# ServoExpanderPCB.net
KiCad netlist of a schematic drawn in Altium Designer
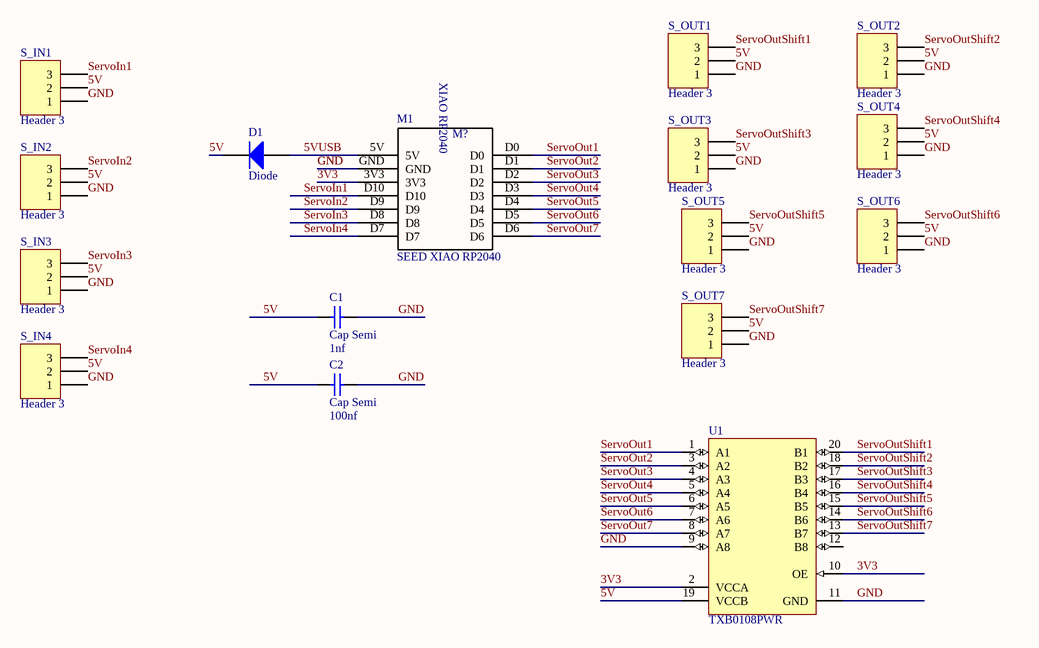
[diagram p0: ServoExpanderPCB.SchDoc]

(export (version "E")
  (design (tool "Eeschema 10.0.6"))
  (components
    (comp (ref "C1")
      (value "Cap Semi")
      (footprint "6-0805_M")
      (description "Capacitor (Semiconductor SIM Model)")
      (fields (field (name "ALTIUM_VALUE") "1nf") (field (name "PUBLISHER") "Altium Limited"))
      (libsource (lib "Miscellaneous Devices") (part "Cap Semi"))
    )
    (comp (ref "C2")
      (value "Cap Semi")
      (footprint "6-0805_M")
      (description "Capacitor (Semiconductor SIM Model)")
      (fields (field (name "ALTIUM_VALUE") "100nf") (field (name "PUBLISHER") "Altium Limited"))
      (libsource (lib "Miscellaneous Devices") (part "Cap Semi"))
    )
    (comp (ref "D1")
      (value "Diode")
      (footprint "6-0805_M")
      (description "Default Diode")
      (fields (field (name "PUBLISHER") "Altium Limited"))
      (libsource (lib "Miscellaneous Devices") (part "Diode"))
    )
    (comp (ref "M1")
      (value "SEED XIAO RP2040")
      (footprint "XIAO RP2040")
      (libsource (lib "RP2040Library") (part "SEED XIAO RP2040"))
    )
    (comp (ref "S_IN1")
      (value "Header 3")
      (footprint "HDR1X3")
      (description "Header, 3-Pin")
      (fields (field (name "PUBLISHER") "Altium Limited"))
      (libsource (lib "Miscellaneous Connectors") (part "Header 3"))
    )
    (comp (ref "S_IN2")
      (value "Header 3")
      (footprint "HDR1X3")
      (description "Header, 3-Pin")
      (fields (field (name "PUBLISHER") "Altium Limited"))
      (libsource (lib "Miscellaneous Connectors") (part "Header 3"))
    )
    (comp (ref "S_IN3")
      (value "Header 3")
      (footprint "HDR1X3")
      (description "Header, 3-Pin")
      (fields (field (name "PUBLISHER") "Altium Limited"))
      (libsource (lib "Miscellaneous Connectors") (part "Header 3"))
    )
    (comp (ref "S_IN4")
      (value "Header 3")
      (footprint "HDR1X3")
      (description "Header, 3-Pin")
      (fields (field (name "PUBLISHER") "Altium Limited"))
      (libsource (lib "Miscellaneous Connectors") (part "Header 3"))
    )
    (comp (ref "S_OUT1")
      (value "Header 3")
      (footprint "HDR1X3")
      (description "Header, 3-Pin")
      (fields (field (name "PUBLISHER") "Altium Limited"))
      (libsource (lib "Miscellaneous Connectors") (part "Header 3"))
    )
    (comp (ref "S_OUT2")
      (value "Header 3")
      (footprint "HDR1X3")
      (description "Header, 3-Pin")
      (fields (field (name "PUBLISHER") "Altium Limited"))
      (libsource (lib "Miscellaneous Connectors") (part "Header 3"))
    )
    (comp (ref "S_OUT3")
      (value "Header 3")
      (footprint "HDR1X3")
      (description "Header, 3-Pin")
      (fields (field (name "PUBLISHER") "Altium Limited"))
      (libsource (lib "Miscellaneous Connectors") (part "Header 3"))
    )
    (comp (ref "S_OUT4")
      (value "Header 3")
      (footprint "HDR1X3")
      (description "Header, 3-Pin")
      (fields (field (name "PUBLISHER") "Altium Limited"))
      (libsource (lib "Miscellaneous Connectors") (part "Header 3"))
    )
    (comp (ref "S_OUT5")
      (value "Header 3")
      (footprint "HDR1X3")
      (description "Header, 3-Pin")
      (fields (field (name "PUBLISHER") "Altium Limited"))
      (libsource (lib "Miscellaneous Connectors") (part "Header 3"))
    )
    (comp (ref "S_OUT6")
      (value "Header 3")
      (footprint "HDR1X3")
      (description "Header, 3-Pin")
      (fields (field (name "PUBLISHER") "Altium Limited"))
      (libsource (lib "Miscellaneous Connectors") (part "Header 3"))
    )
    (comp (ref "S_OUT7")
      (value "Header 3")
      (footprint "HDR1X3")
      (description "Header, 3-Pin")
      (fields (field (name "PUBLISHER") "Altium Limited"))
      (libsource (lib "Miscellaneous Connectors") (part "Header 3"))
    )
    (comp (ref "U1")
      (value "TXB0108PWR")
      (footprint "PW0020A_L")
      (fields (field (name "MANUFACTURER") "Texas Instruments"))
      (libsource (lib "Altium Content Vault") (part "TI-TXB0108-PW-20"))
    )
  )
  (nets
    (net (code "1") (name "/3V3") (class "Default")
      (node (ref "M1") (pin "3V3") (pinfunction "3V3_3V3") (pintype "passive"))
      (node (ref "U1") (pin "10") (pinfunction "OE_10") (pintype "input"))
      (node (ref "U1") (pin "2") (pinfunction "VCCA_2") (pintype "power_in"))
    )
    (net (code "2") (name "/5V") (class "Default")
      (node (ref "C1") (pin "1") (pinfunction "1_1") (pintype "passive"))
      (node (ref "C2") (pin "1") (pinfunction "1_1") (pintype "passive"))
      (node (ref "D1") (pin "2") (pinfunction "K_2") (pintype "passive"))
      (node (ref "S_IN1") (pin "2") (pinfunction "2_2") (pintype "passive"))
      (node (ref "S_IN2") (pin "2") (pinfunction "2_2") (pintype "passive"))
      (node (ref "S_IN3") (pin "2") (pinfunction "2_2") (pintype "passive"))
      (node (ref "S_IN4") (pin "2") (pinfunction "2_2") (pintype "passive"))
      (node (ref "S_OUT1") (pin "2") (pinfunction "2_2") (pintype "passive"))
      (node (ref "S_OUT2") (pin "2") (pinfunction "2_2") (pintype "passive"))
      (node (ref "S_OUT3") (pin "2") (pinfunction "2_2") (pintype "passive"))
      (node (ref "S_OUT4") (pin "2") (pinfunction "2_2") (pintype "passive"))
      (node (ref "S_OUT5") (pin "2") (pinfunction "2_2") (pintype "passive"))
      (node (ref "S_OUT6") (pin "2") (pinfunction "2_2") (pintype "passive"))
      (node (ref "S_OUT7") (pin "2") (pinfunction "2_2") (pintype "passive"))
      (node (ref "U1") (pin "19") (pinfunction "VCCB_19") (pintype "power_in"))
    )
    (net (code "3") (name "/5VUSB") (class "Default")
      (node (ref "D1") (pin "1") (pinfunction "A_1") (pintype "passive"))
      (node (ref "M1") (pin "5V") (pinfunction "5V_5V") (pintype "passive"))
    )
    (net (code "4") (name "/GND") (class "Default")
      (node (ref "C1") (pin "2") (pinfunction "2_2") (pintype "passive"))
      (node (ref "C2") (pin "2") (pinfunction "2_2") (pintype "passive"))
      (node (ref "M1") (pin "GND") (pinfunction "GND_GND") (pintype "passive"))
      (node (ref "S_IN1") (pin "1") (pinfunction "1_1") (pintype "passive"))
      (node (ref "S_IN2") (pin "1") (pinfunction "1_1") (pintype "passive"))
      (node (ref "S_IN3") (pin "1") (pinfunction "1_1") (pintype "passive"))
      (node (ref "S_IN4") (pin "1") (pinfunction "1_1") (pintype "passive"))
      (node (ref "S_OUT1") (pin "1") (pinfunction "1_1") (pintype "passive"))
      (node (ref "S_OUT2") (pin "1") (pinfunction "1_1") (pintype "passive"))
      (node (ref "S_OUT3") (pin "1") (pinfunction "1_1") (pintype "passive"))
      (node (ref "S_OUT4") (pin "1") (pinfunction "1_1") (pintype "passive"))
      (node (ref "S_OUT5") (pin "1") (pinfunction "1_1") (pintype "passive"))
      (node (ref "S_OUT6") (pin "1") (pinfunction "1_1") (pintype "passive"))
      (node (ref "S_OUT7") (pin "1") (pinfunction "1_1") (pintype "passive"))
      (node (ref "U1") (pin "11") (pinfunction "GND_11") (pintype "power_in"))
      (node (ref "U1") (pin "9") (pinfunction "A8_9") (pintype "bidirectional"))
    )
    (net (code "5") (name "/ServoIn1") (class "Default")
      (node (ref "M1") (pin "D10") (pinfunction "D10_D10") (pintype "passive"))
      (node (ref "S_IN1") (pin "3") (pinfunction "3_3") (pintype "passive"))
    )
    (net (code "6") (name "/ServoIn2") (class "Default")
      (node (ref "M1") (pin "D9") (pinfunction "D9_D9") (pintype "passive"))
      (node (ref "S_IN2") (pin "3") (pinfunction "3_3") (pintype "passive"))
    )
    (net (code "7") (name "/ServoIn3") (class "Default")
      (node (ref "M1") (pin "D8") (pinfunction "D8_D8") (pintype "passive"))
      (node (ref "S_IN3") (pin "3") (pinfunction "3_3") (pintype "passive"))
    )
    (net (code "8") (name "/ServoIn4") (class "Default")
      (node (ref "M1") (pin "D7") (pinfunction "D7_D7") (pintype "passive"))
      (node (ref "S_IN4") (pin "3") (pinfunction "3_3") (pintype "passive"))
    )
    (net (code "9") (name "/ServoOut1") (class "Default")
      (node (ref "M1") (pin "D0") (pinfunction "D0_D0") (pintype "passive"))
      (node (ref "U1") (pin "1") (pinfunction "A1_1") (pintype "bidirectional"))
    )
    (net (code "10") (name "/ServoOut2") (class "Default")
      (node (ref "M1") (pin "D1") (pinfunction "D1_D1") (pintype "passive"))
      (node (ref "U1") (pin "3") (pinfunction "A2_3") (pintype "bidirectional"))
    )
    (net (code "11") (name "/ServoOut3") (class "Default")
      (node (ref "M1") (pin "D2") (pinfunction "D2_D2") (pintype "passive"))
      (node (ref "U1") (pin "4") (pinfunction "A3_4") (pintype "bidirectional"))
    )
    (net (code "12") (name "/ServoOut4") (class "Default")
      (node (ref "M1") (pin "D3") (pinfunction "D3_D3") (pintype "passive"))
      (node (ref "U1") (pin "5") (pinfunction "A4_5") (pintype "bidirectional"))
    )
    (net (code "13") (name "/ServoOut5") (class "Default")
      (node (ref "M1") (pin "D4") (pinfunction "D4_D4") (pintype "passive"))
      (node (ref "U1") (pin "6") (pinfunction "A5_6") (pintype "bidirectional"))
    )
    (net (code "14") (name "/ServoOut6") (class "Default")
      (node (ref "M1") (pin "D5") (pinfunction "D5_D5") (pintype "passive"))
      (node (ref "U1") (pin "7") (pinfunction "A6_7") (pintype "bidirectional"))
    )
    (net (code "15") (name "/ServoOut7") (class "Default")
      (node (ref "M1") (pin "D6") (pinfunction "D6_D6") (pintype "passive"))
      (node (ref "U1") (pin "8") (pinfunction "A7_8") (pintype "bidirectional"))
    )
    (net (code "16") (name "/ServoOutShift1") (class "Default")
      (node (ref "S_OUT1") (pin "3") (pinfunction "3_3") (pintype "passive"))
      (node (ref "U1") (pin "20") (pinfunction "B1_20") (pintype "bidirectional"))
    )
    (net (code "17") (name "/ServoOutShift2") (class "Default")
      (node (ref "S_OUT2") (pin "3") (pinfunction "3_3") (pintype "passive"))
      (node (ref "U1") (pin "18") (pinfunction "B2_18") (pintype "bidirectional"))
    )
    (net (code "18") (name "/ServoOutShift3") (class "Default")
      (node (ref "S_OUT3") (pin "3") (pinfunction "3_3") (pintype "passive"))
      (node (ref "U1") (pin "17") (pinfunction "B3_17") (pintype "bidirectional"))
    )
    (net (code "19") (name "/ServoOutShift4") (class "Default")
      (node (ref "S_OUT4") (pin "3") (pinfunction "3_3") (pintype "passive"))
      (node (ref "U1") (pin "16") (pinfunction "B4_16") (pintype "bidirectional"))
    )
    (net (code "20") (name "/ServoOutShift5") (class "Default")
      (node (ref "S_OUT5") (pin "3") (pinfunction "3_3") (pintype "passive"))
      (node (ref "U1") (pin "15") (pinfunction "B5_15") (pintype "bidirectional"))
    )
    (net (code "21") (name "/ServoOutShift6") (class "Default")
      (node (ref "S_OUT6") (pin "3") (pinfunction "3_3") (pintype "passive"))
      (node (ref "U1") (pin "14") (pinfunction "B6_14") (pintype "bidirectional"))
    )
    (net (code "22") (name "/ServoOutShift7") (class "Default")
      (node (ref "S_OUT7") (pin "3") (pinfunction "3_3") (pintype "passive"))
      (node (ref "U1") (pin "13") (pinfunction "B7_13") (pintype "bidirectional"))
    )
    (net (code "23") (name "unconnected-(U1-B8-Pad12)") (class "Default")
      (node (ref "U1") (pin "12") (pinfunction "B8_12") (pintype "bidirectional"))
    )
  )
)
